# AC_Conversion_and_Power.net
KiCad netlist of a schematic drawn in Altium Designer
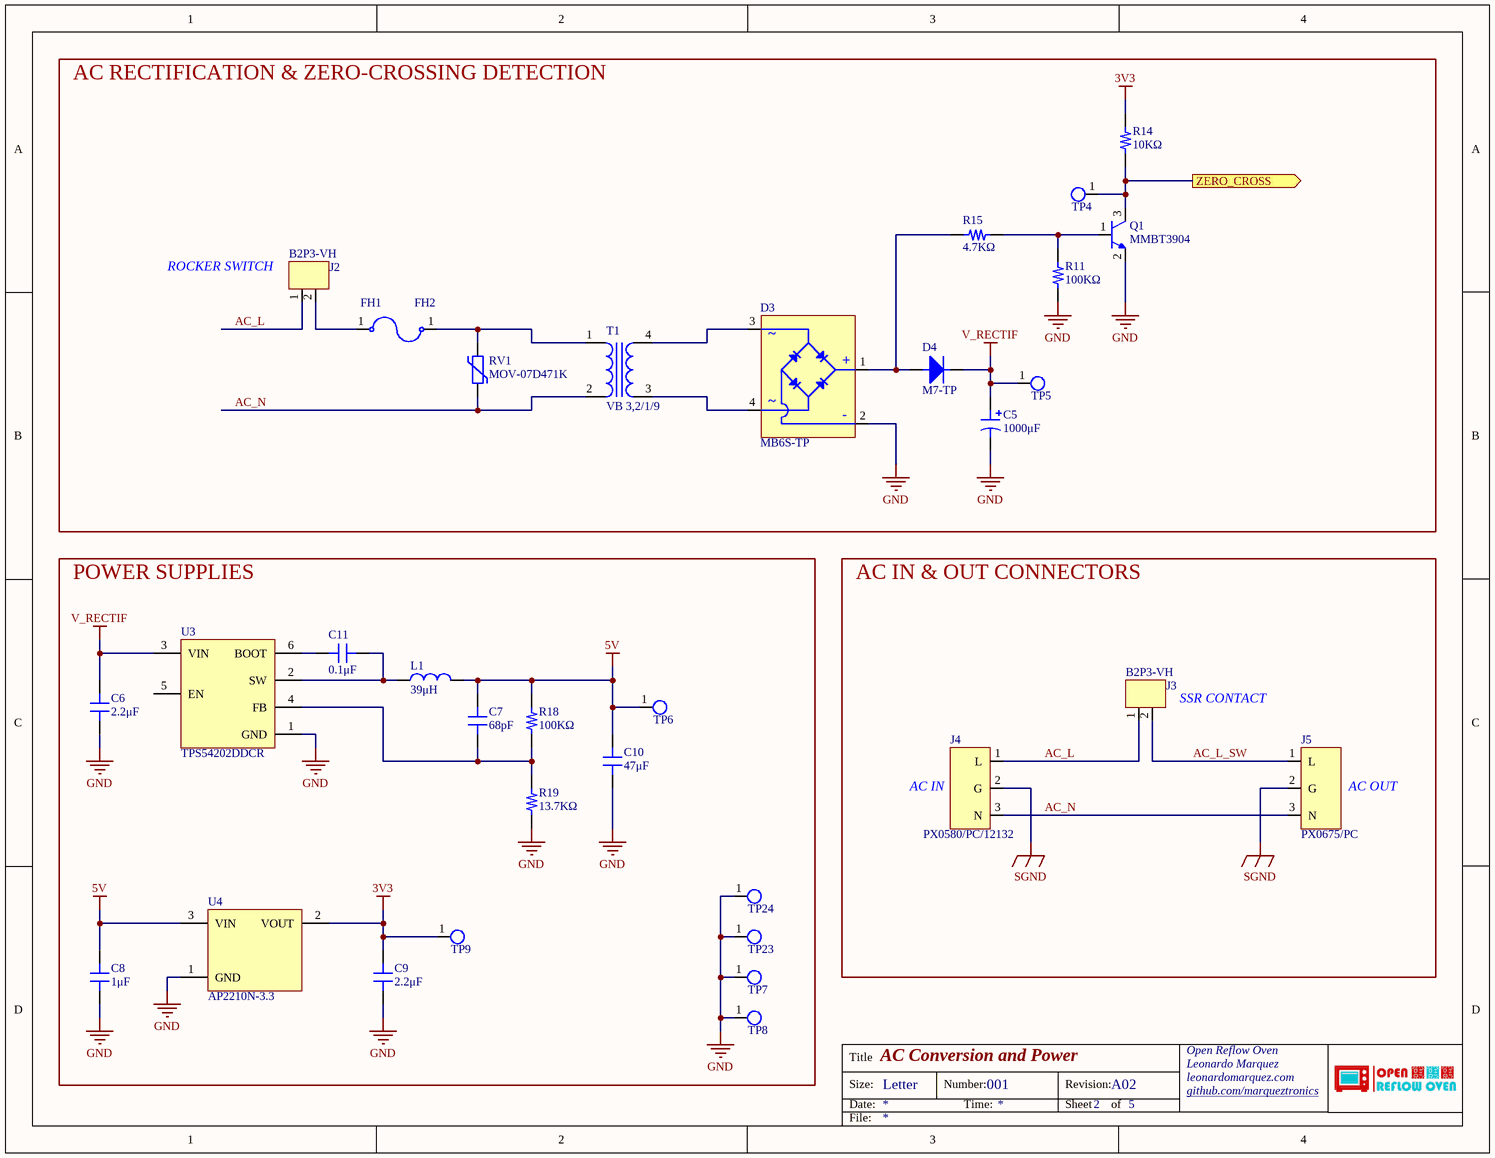
[diagram p0: AC Conversion and Power.SchDoc]

(export (version "E")
  (design (tool "Eeschema 10.0.6"))
  (components
    (comp (ref "C5")
      (value "1000μF")
      (footprint "CPOL10X20")
      (fields
        (field (name "MANUFACTURER") "Rubycon")
        (field (name "MANUFACTURER PART NUMBER") "16YXF1000MEFC10X20")
      )
      (libsource (lib "REFLOW_CONTROLLER") (part "C-1000UF-16V-CPOL10X20"))
    )
    (comp (ref "C6")
      (value "2.2μF")
      (footprint "C0805")
      (description "35V 2.2uF X7R ±10% 0805 Multilayer Ceramic Capacitors MLCC - SMD/SMT ROHS")
      (fields
        (field (name "MANUFACTURER") "TDK")
        (field (name "MANUFACTURER PART NUMBER") "CGA4J1X7R1V225KT0Y0E")
      )
      (libsource (lib "REFLOW_CONTROLLER") (part "C-2.2UF-35V-X7R-C0805"))
    )
    (comp (ref "C7")
      (value "68pF")
      (footprint "C0603")
      (description "50V 68pF NP0 ±5% 0603 Multilayer Ceramic Capacitors MLCC - SMD/SMT ROHS")
      (fields
        (field (name "MANUFACTURER") "Yageo")
        (field (name "MANUFACTURER PART NUMBER") "CC0603JRNPO9BN680")
      )
      (libsource (lib "REFLOW_CONTROLLER") (part "C-68PF-50V-NP0-C0603"))
    )
    (comp (ref "C8")
      (value "1μF")
      (footprint "C0603")
      (description "16V 1uF X7R ±10% 0603 Multilayer Ceramic Capacitors MLCC - SMD/SMT ROHS")
      (fields
        (field (name "MANUFACTURER") "Samsung Electro-Mechanics")
        (field (name "MANUFACTURER PART NUMBER") "CL10B105KO8NNNC")
      )
      (libsource (lib "REFLOW_CONTROLLER") (part "C-1UF-16V-X7R-C0603"))
    )
    (comp (ref "C9")
      (value "2.2μF")
      (footprint "C0805")
      (description "35V 2.2uF X7R ±10% 0805 Multilayer Ceramic Capacitors MLCC - SMD/SMT ROHS")
      (fields
        (field (name "MANUFACTURER") "TDK")
        (field (name "MANUFACTURER PART NUMBER") "CGA4J1X7R1V225KT0Y0E")
      )
      (libsource (lib "REFLOW_CONTROLLER") (part "C-2.2UF-35V-X7R-C0805"))
    )
    (comp (ref "C10")
      (value "47μF")
      (footprint "C1210")
      (description "16V 47uF X5R ±10% 1210 Multilayer Ceramic Capacitors MLCC - SMD/SMT ROHS")
      (fields
        (field (name "MANUFACTURER") "Murata")
        (field (name "MANUFACTURER PART NUMBER") "GRM32ER61C476KE15L")
      )
      (libsource (lib "REFLOW_CONTROLLER") (part "C-47UF-16V-X5R-C1210"))
    )
    (comp (ref "C11")
      (value "0.1μF")
      (footprint "C0603")
      (description "50V 100nF X7R ±10% 0603 Multilayer Ceramic Capacitors MLCC - SMD/SMT ROHS")
      (fields
        (field (name "MANUFACTURER") "Samsung Electro-Mechanics")
        (field (name "MANUFACTURER PART NUMBER") "CL10B104KB8NNNC")
      )
      (libsource (lib "REFLOW_CONTROLLER") (part "C-0.1UF-50V-X7R-C0603"))
    )
    (comp (ref "D3")
      (value "MB6S-TP")
      (footprint "MBS-1")
      (description "35A 1V@400mA 800mA 600V MBS Bridge Rectifiers ROHS")
      (fields (field (name "MANUFACTURER") "Micro Commercial Components"))
      (libsource (lib "REFLOW_CONTROLLER") (part "D-BRIDGE-RECTIFIER-600V-0.5A-MBS-1"))
    )
    (comp (ref "D4")
      (value "M7-TP")
      (footprint "DO-214AC")
      (description "1A 1kV 1.1V@1A SMA(DO-214AC) Diodes - General Purpose ROHS")
      (fields (field (name "MANUFACTURER") "Micro Commercial Components"))
      (libsource (lib "REFLOW_CONTROLLER") (part "D-1KV-1A-DO-214AC"))
    )
    (comp (ref "FH1")
      (value "01000020Z")
      (footprint "100-020")
      (description "Circuit Board Mount Fuse Clips for 5mm Diameter Fuses")
      (fields (field (name "MANUFACTURER") "Littelfuse"))
      (libsource (lib "REFLOW_CONTROLLER") (part "FH-1P-5X20MM-100-020"))
    )
    (comp (ref "FH2")
      (value "01000020Z")
      (footprint "100-020")
      (description "Circuit Board Mount Fuse Clips for 5mm Diameter Fuses")
      (fields (field (name "MANUFACTURER") "Littelfuse"))
      (libsource (lib "REFLOW_CONTROLLER") (part "FH-1P-5X20MM-100-020"))
    )
    (comp (ref "J2")
      (value "B2P3-VH")
      (footprint "B2P3-VH")
      (description "1x2P 2P VH 1 7.92mm 2 Brass Plugin,P=7.92mm Wire To Board Connector ROHS")
      (fields (field (name "MANUFACTURER") "JST") (field (name "MANUFACTURER PART NUMBER") "B2P3-VH(LF)(SN)"))
      (libsource (lib "REFLOW_CONTROLLER") (part "J-2P-7.92MM-B2P3-VH"))
    )
    (comp (ref "J3")
      (value "B2P3-VH")
      (footprint "B2P3-VH")
      (description "1x2P 2P VH 1 7.92mm 2 Brass Plugin,P=7.92mm Wire To Board Connector ROHS")
      (fields (field (name "MANUFACTURER") "JST") (field (name "MANUFACTURER PART NUMBER") "B2P3-VH(LF)(SN)"))
      (libsource (lib "REFLOW_CONTROLLER") (part "J-2P-7.92MM-B2P3-VH"))
    )
    (comp (ref "J4")
      (value "PX0580/PC/12132")
      (footprint "PX0580/PC/12132")
      (description "C14 Right Angle Panel Mount, PCB Mount IEC Connector Male, 10A, 250 V")
      (fields (field (name "MANUFACTURER") "Bulgin"))
      (libsource (lib "REFLOW_CONTROLLER") (part "J-3P-IEC-C14-PX0580/PC/12132"))
    )
    (comp (ref "J5")
      (value "PX0675/PC")
      (footprint "PX0675/PC")
      (description "C13 Right Angle Panel Mount, PCB Mount IEC Connector Socket, 10A, 250 V")
      (fields (field (name "MANUFACTURER") "Bulgin"))
      (libsource (lib "REFLOW_CONTROLLER") (part "J-3P-IEC-C14-PX0675/PC"))
    )
    (comp (ref "L1")
      (value "39μH")
      (footprint "L_ASPI-0602S")
      (description "860mA 39uH ±20% SMD,6.7x6.7mm Power Inductors ROHS")
      (fields
        (field (name "MANUFACTURER") "Abracon")
        (field (name "MANUFACTURER PART NUMBER") "ASPI-0602S-390M-T")
      )
      (libsource (lib "REFLOW_CONTROLLER") (part "L-39UH-860MA-L_ASPI-0602S"))
    )
    (comp (ref "Q1")
      (value "MMBT3904")
      (footprint "SOT-23")
      (description "40V 250mW 200mA NPN SOT-23 Bipolar Transistors - BJT ROHS")
      (fields (field (name "MANUFACTURER") "Nexperia"))
      (libsource (lib "REFLOW_CONTROLLER") (part "Q-NPN-40V-0.2A-SOT-23"))
    )
    (comp (ref "R11")
      (value "100KΩ")
      (footprint "R0603")
      (description "100mW Thick Film Resistors 75V ±100ppm/℃ ±1% 100kΩ 0603 Chip Resistor - Surface Mount ROHS")
      (fields
        (field (name "MANUFACTURER") "Yageo")
        (field (name "MANUFACTURER PART NUMBER") "RC0603FR-07100KL")
      )
      (libsource (lib "REFLOW_CONTROLLER") (part "R-100K-1/10W-R0603"))
    )
    (comp (ref "R14")
      (value "10KΩ")
      (footprint "R0603")
      (description "100mW Thick Film Resistors 75V ±100ppm/℃ ±1% 10kΩ 0603 Chip Resistor - Surface Mount ROHS")
      (fields
        (field (name "MANUFACTURER") "Yageo")
        (field (name "MANUFACTURER PART NUMBER") "RC0603FR-0710KL")
      )
      (libsource (lib "REFLOW_CONTROLLER") (part "R-10K-1/10W-R0603"))
    )
    (comp (ref "R15")
      (value "4.7KΩ")
      (footprint "R0603")
      (description "100mW Thick Film Resistors 75V ±100ppm/℃ ±1% 4.7kΩ 0603 Chip Resistor - Surface Mount ROHS")
      (fields
        (field (name "MANUFACTURER") "Yageo")
        (field (name "MANUFACTURER PART NUMBER") "RC0603FR-074K7L")
      )
      (libsource (lib "REFLOW_CONTROLLER") (part "R-4.7K-1/10W-R0603"))
    )
    (comp (ref "R18")
      (value "100KΩ")
      (footprint "R0603")
      (description "100mW Thick Film Resistors 75V ±100ppm/℃ ±1% 100kΩ 0603 Chip Resistor - Surface Mount ROHS")
      (fields
        (field (name "MANUFACTURER") "Yageo")
        (field (name "MANUFACTURER PART NUMBER") "RC0603FR-07100KL")
      )
      (libsource (lib "REFLOW_CONTROLLER") (part "R-100K-1/10W-R0603"))
    )
    (comp (ref "R19")
      (value "13.7KΩ")
      (footprint "R0603")
      (description "100mW Thick Film Resistors 75V ±100ppm/℃ ±1% 13.7kΩ 0603 Chip Resistor - Surface Mount ROHS")
      (fields
        (field (name "MANUFACTURER") "Yageo")
        (field (name "MANUFACTURER PART NUMBER") "RC0603FR-0713K7L")
      )
      (libsource (lib "REFLOW_CONTROLLER") (part "R-13.7K-1/10W-R0603"))
    )
    (comp (ref "RV1")
      (value "MOV-07D471K")
      (footprint "MOV-07D471K")
      (description "VARISTOR 470V 1.2KA DISC 7MM")
      (fields (field (name "MANUFACTURER") "Bourns"))
      (libsource (lib "REFLOW_CONTROLLER") (part "RV-470V-1.2KA-MOV-07D471K"))
    )
    (comp (ref "T1")
      (value "VB 3,2/1/9")
      (footprint "VB_3,2/1/9")
      (description "Block 9V ac 1 Output Through Hole PCB Transformer, 3.2VA")
      (fields (field (name "MANUFACTURER") "Block"))
      (libsource (lib "REFLOW_CONTROLLER") (part "T-230V-9V-VB_3,2/1/9"))
    )
    (comp (ref "TP4")
      (value "TP-1MM-ROUND")
      (footprint "TP-1MM-ROUND")
      (description "Round Test Point 1mm Dia")
      (libsource (lib "REFLOW_CONTROLLER") (part "TP-1MM-ROUND"))
    )
    (comp (ref "TP5")
      (value "TP-1MM-ROUND")
      (footprint "TP-1MM-ROUND")
      (description "Round Test Point 1mm Dia")
      (libsource (lib "REFLOW_CONTROLLER") (part "TP-1MM-ROUND"))
    )
    (comp (ref "TP6")
      (value "TP-1MM-ROUND")
      (footprint "TP-1MM-ROUND")
      (description "Round Test Point 1mm Dia")
      (libsource (lib "REFLOW_CONTROLLER") (part "TP-1MM-ROUND"))
    )
    (comp (ref "TP7")
      (value "TP-1MM-ROUND")
      (footprint "TP-1MM-ROUND")
      (description "Round Test Point 1mm Dia")
      (libsource (lib "REFLOW_CONTROLLER") (part "TP-1MM-ROUND"))
    )
    (comp (ref "TP8")
      (value "TP-1MM-ROUND")
      (footprint "TP-1MM-ROUND")
      (description "Round Test Point 1mm Dia")
      (libsource (lib "REFLOW_CONTROLLER") (part "TP-1MM-ROUND"))
    )
    (comp (ref "TP9")
      (value "TP-1MM-ROUND")
      (footprint "TP-1MM-ROUND")
      (description "Round Test Point 1mm Dia")
      (libsource (lib "REFLOW_CONTROLLER") (part "TP-1MM-ROUND"))
    )
    (comp (ref "TP23")
      (value "TP-1MM-ROUND")
      (footprint "TP-1MM-ROUND")
      (description "Round Test Point 1mm Dia")
      (libsource (lib "REFLOW_CONTROLLER") (part "TP-1MM-ROUND"))
    )
    (comp (ref "TP24")
      (value "TP-1MM-ROUND")
      (footprint "TP-1MM-ROUND")
      (description "Round Test Point 1mm Dia")
      (libsource (lib "REFLOW_CONTROLLER") (part "TP-1MM-ROUND"))
    )
    (comp (ref "U3")
      (value "TPS54202DDCR")
      (footprint "SOT-23-6")
      (description "4.5-V to 28-V Input, 2-A Output, EMI Friendly  Synchronous Step Down Converter")
      (fields (field (name "MANUFACTURER") "Texas Instruments"))
      (libsource (lib "REFLOW_CONTROLLER") (part "U-TPS54202DDCR-SOT-23-6"))
    )
    (comp (ref "U4")
      (value "AP2210N-3.3")
      (footprint "SOT-23")
      (description "300mA 75dB@(100Hz) Fixed 3.3V Positive electrode 13.2V SOT-23 Linear Voltage Regulators (LDO) ROHS")
      (fields
        (field (name "MANUFACTURER") "Diodes Incorporated")
        (field (name "MANUFACTURER PART NUMBER") "AP2210N-3.3TRG1")
      )
      (libsource (lib "REFLOW_CONTROLLER") (part "U-AP2210N-3.3TRG1-SOT-23"))
    )
  )
  (nets
    (net (code "1") (name "/AC_L") (class "Default")
      (node (ref "J2") (pin "1") (pinfunction "1_1") (pintype "passive"))
      (node (ref "J3") (pin "1") (pinfunction "1_1") (pintype "passive"))
      (node (ref "J4") (pin "1") (pinfunction "L_1") (pintype "passive"))
    )
    (net (code "2") (name "/AC_L_SW") (class "Default")
      (node (ref "J3") (pin "2") (pinfunction "2_2") (pintype "passive"))
      (node (ref "J5") (pin "1") (pinfunction "L_1") (pintype "passive"))
    )
    (net (code "3") (name "/AC_N") (class "Default")
      (node (ref "J4") (pin "3") (pinfunction "N_3") (pintype "passive"))
      (node (ref "J5") (pin "3") (pinfunction "N_3") (pintype "passive"))
      (node (ref "RV1") (pin "1") (pinfunction "1_1") (pintype "passive"))
      (node (ref "T1") (pin "2") (pinfunction "2_2") (pintype "passive"))
    )
    (net (code "4") (name "/ZERO_CROSS") (class "Default")
      (node (ref "Q1") (pin "3") (pinfunction "C_3") (pintype "passive"))
      (node (ref "R14") (pin "1") (pinfunction "1_1") (pintype "passive"))
      (node (ref "TP4") (pin "1") (pinfunction "1_1") (pintype "passive"))
    )
    (net (code "5") (name "3V3") (class "Default")
      (node (ref "C9") (pin "2") (pinfunction "2_2") (pintype "passive"))
      (node (ref "R14") (pin "2") (pinfunction "2_2") (pintype "passive"))
      (node (ref "TP9") (pin "1") (pinfunction "1_1") (pintype "passive"))
      (node (ref "U4") (pin "2") (pinfunction "VOUT_2") (pintype "passive"))
    )
    (net (code "6") (name "5V") (class "Default")
      (node (ref "C10") (pin "2") (pinfunction "2_2") (pintype "passive"))
      (node (ref "C7") (pin "2") (pinfunction "2_2") (pintype "passive"))
      (node (ref "C8") (pin "2") (pinfunction "2_2") (pintype "passive"))
      (node (ref "L1") (pin "2") (pinfunction "2_2") (pintype "passive"))
      (node (ref "R18") (pin "2") (pinfunction "2_2") (pintype "passive"))
      (node (ref "TP6") (pin "1") (pinfunction "1_1") (pintype "passive"))
      (node (ref "U4") (pin "3") (pinfunction "VIN_3") (pintype "passive"))
    )
    (net (code "7") (name "GND") (class "Default")
      (node (ref "C10") (pin "1") (pinfunction "1_1") (pintype "passive"))
      (node (ref "C5") (pin "2") (pinfunction "2_2") (pintype "passive"))
      (node (ref "C6") (pin "1") (pinfunction "1_1") (pintype "passive"))
      (node (ref "C8") (pin "1") (pinfunction "1_1") (pintype "passive"))
      (node (ref "C9") (pin "1") (pinfunction "1_1") (pintype "passive"))
      (node (ref "D3") (pin "2") (pinfunction "-_2") (pintype "passive"))
      (node (ref "Q1") (pin "2") (pinfunction "E_2") (pintype "passive"))
      (node (ref "R11") (pin "1") (pinfunction "1_1") (pintype "passive"))
      (node (ref "R19") (pin "1") (pinfunction "1_1") (pintype "passive"))
      (node (ref "TP23") (pin "1") (pinfunction "1_1") (pintype "passive"))
      (node (ref "TP24") (pin "1") (pinfunction "1_1") (pintype "passive"))
      (node (ref "TP7") (pin "1") (pinfunction "1_1") (pintype "passive"))
      (node (ref "TP8") (pin "1") (pinfunction "1_1") (pintype "passive"))
      (node (ref "U3") (pin "1") (pinfunction "GND_1") (pintype "passive"))
      (node (ref "U4") (pin "1") (pinfunction "GND_1") (pintype "passive"))
    )
    (net (code "8") (name "Net-(D3-+)") (class "Default")
      (node (ref "D3") (pin "1") (pinfunction "+_1") (pintype "passive"))
      (node (ref "D4") (pin "A") (pinfunction "A_A") (pintype "passive"))
      (node (ref "R15") (pin "1") (pinfunction "1_1") (pintype "passive"))
    )
    (net (code "9") (name "Net-(D3-~-Pad3)") (class "Default")
      (node (ref "D3") (pin "3") (pinfunction "~_3") (pintype "passive"))
      (node (ref "T1") (pin "4") (pinfunction "4_4") (pintype "passive"))
    )
    (net (code "10") (name "Net-(D3-~-Pad4)") (class "Default")
      (node (ref "D3") (pin "4") (pinfunction "~_4") (pintype "passive"))
      (node (ref "T1") (pin "3") (pinfunction "3_3") (pintype "passive"))
    )
    (net (code "11") (name "Net-(FH1-Pad1)") (class "Default")
      (node (ref "FH1") (pin "1") (pinfunction "1_1") (pintype "passive"))
      (node (ref "J2") (pin "2") (pinfunction "2_2") (pintype "passive"))
    )
    (net (code "12") (name "Net-(FH2-Pad1)") (class "Default")
      (node (ref "FH2") (pin "1") (pinfunction "1_1") (pintype "passive"))
      (node (ref "RV1") (pin "2") (pinfunction "2_2") (pintype "passive"))
      (node (ref "T1") (pin "1") (pinfunction "1_1") (pintype "passive"))
    )
    (net (code "13") (name "Net-(Q1-B)") (class "Default")
      (node (ref "Q1") (pin "1") (pinfunction "B_1") (pintype "passive"))
      (node (ref "R11") (pin "2") (pinfunction "2_2") (pintype "passive"))
      (node (ref "R15") (pin "2") (pinfunction "2_2") (pintype "passive"))
    )
    (net (code "14") (name "Net-(U3-BOOT)") (class "Default")
      (node (ref "C11") (pin "2") (pinfunction "2_2") (pintype "passive"))
      (node (ref "U3") (pin "6") (pinfunction "BOOT_6") (pintype "passive"))
    )
    (net (code "15") (name "Net-(U3-FB)") (class "Default")
      (node (ref "C7") (pin "1") (pinfunction "1_1") (pintype "passive"))
      (node (ref "R18") (pin "1") (pinfunction "1_1") (pintype "passive"))
      (node (ref "R19") (pin "2") (pinfunction "2_2") (pintype "passive"))
      (node (ref "U3") (pin "4") (pinfunction "FB_4") (pintype "passive"))
    )
    (net (code "16") (name "Net-(U3-SW)") (class "Default")
      (node (ref "C11") (pin "1") (pinfunction "1_1") (pintype "passive"))
      (node (ref "L1") (pin "1") (pinfunction "1_1") (pintype "passive"))
      (node (ref "U3") (pin "2") (pinfunction "SW_2") (pintype "passive"))
    )
    (net (code "17") (name "SGND") (class "Default")
      (node (ref "J4") (pin "2") (pinfunction "G_2") (pintype "passive"))
      (node (ref "J5") (pin "2") (pinfunction "G_2") (pintype "passive"))
    )
    (net (code "18") (name "V_RECTIF") (class "Default")
      (node (ref "C5") (pin "1") (pinfunction "1_1") (pintype "passive"))
      (node (ref "C6") (pin "2") (pinfunction "2_2") (pintype "passive"))
      (node (ref "D4") (pin "K") (pinfunction "K_K") (pintype "passive"))
      (node (ref "TP5") (pin "1") (pinfunction "1_1") (pintype "passive"))
      (node (ref "U3") (pin "3") (pinfunction "VIN_3") (pintype "passive"))
    )
    (net (code "19") (name "unconnected-(U3-EN-Pad5)") (class "Default")
      (node (ref "U3") (pin "5") (pinfunction "EN_5") (pintype "passive"))
    )
  )
)
